# mcu.net
KiCad netlist of a schematic drawn in Altium Designer
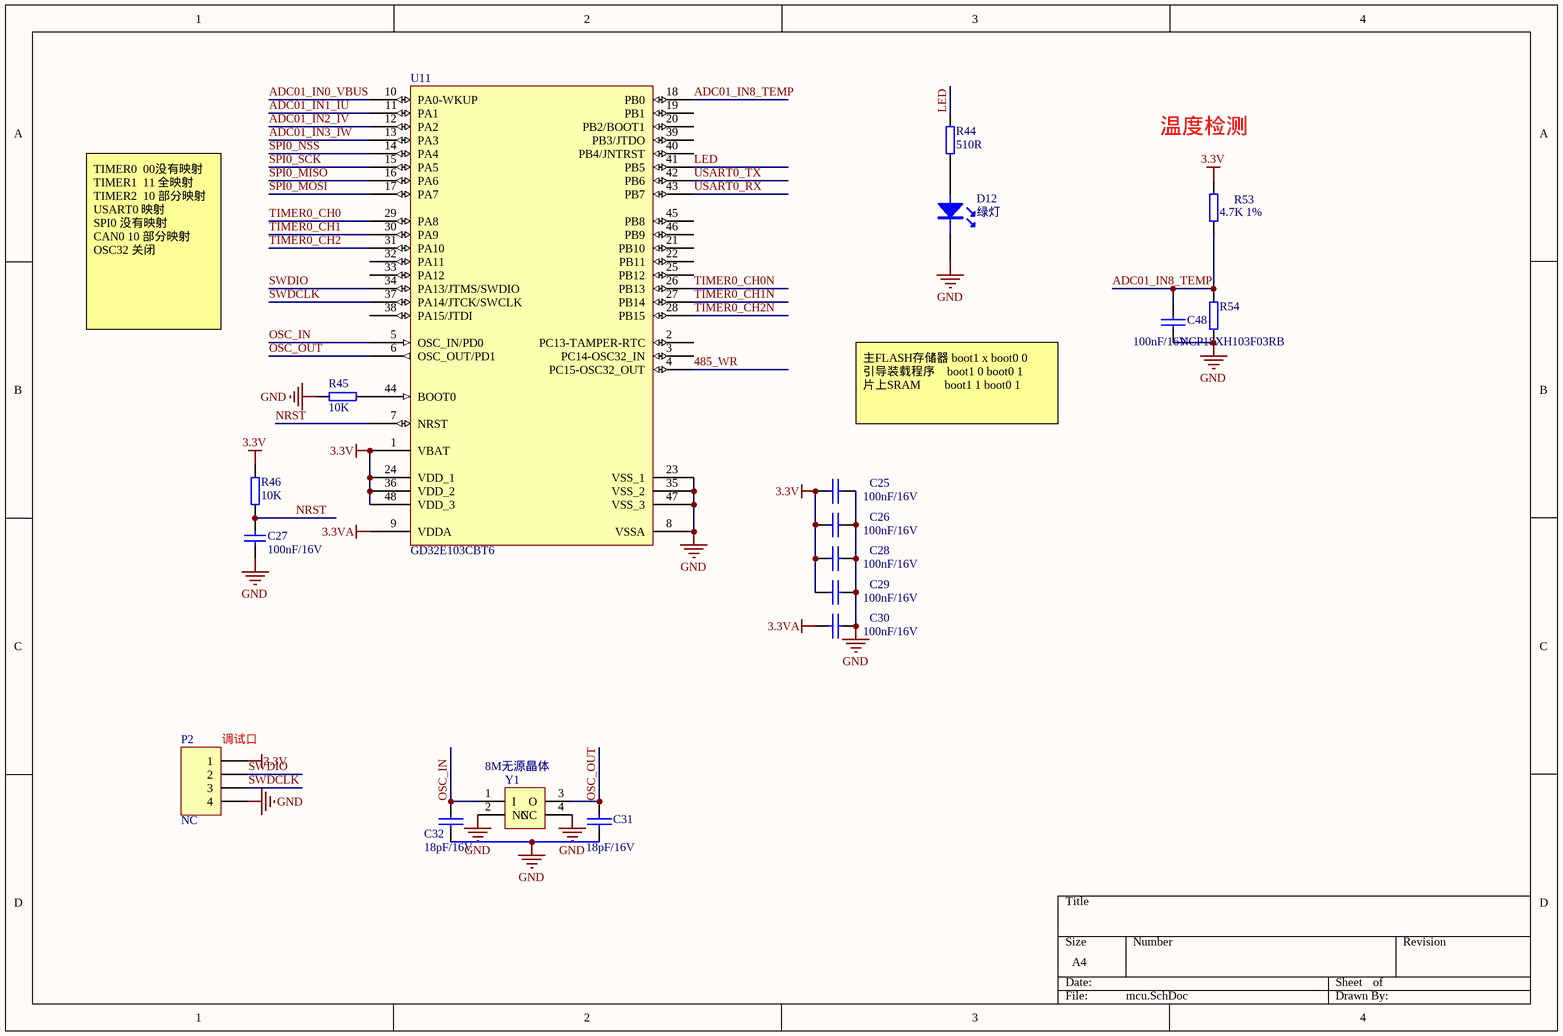
[diagram p0: mcu.SchDoc]

(export (version "E")
  (design (tool "Eeschema 10.0.6"))
  (components
    (comp (ref "C25")
      (value "100nF/16V")
      (footprint "C0402")
      (description "Capacitor")
      (libsource (lib "*") (part "CAP"))
    )
    (comp (ref "C26")
      (value "100nF/16V")
      (footprint "C0402")
      (description "Capacitor")
      (libsource (lib "*") (part "CAP"))
    )
    (comp (ref "C27") (value "100nF/16V") (footprint "C0402") (libsource (lib "zijianku") (part "cap")))
    (comp (ref "C28")
      (value "100nF/16V")
      (footprint "C0402")
      (description "Capacitor")
      (libsource (lib "*") (part "CAP"))
    )
    (comp (ref "C29")
      (value "100nF/16V")
      (footprint "C0402")
      (description "Capacitor")
      (libsource (lib "*") (part "CAP"))
    )
    (comp (ref "C30")
      (value "100nF/16V")
      (footprint "C0402")
      (description "Capacitor")
      (libsource (lib "*") (part "CAP"))
    )
    (comp (ref "C31")
      (value "18pF/16V")
      (footprint "C0402")
      (description "Capacitor")
      (libsource (lib "*") (part "CAP"))
    )
    (comp (ref "C32")
      (value "18pF/16V")
      (footprint "C0402")
      (description "Capacitor")
      (libsource (lib "*") (part "CAP"))
    )
    (comp (ref "C48")
      (value "100nF/16V")
      (footprint "C0402")
      (description "Capacitor")
      (libsource (lib "*") (part "CAP"))
    )
    (comp (ref "D12")
      (value "绿灯")
      (footprint "LED_0603")
      (description "绿灯led")
      (libsource (lib "*") (part "LED"))
    )
    (comp (ref "P2")
      (value "NC")
      (footprint "2.0*4")
      (description "空，无器件")
      (fields (field (name "PUBLISHER") "Altium Limited"))
      (libsource (lib "COMMON") (part "排针2mm,1*4"))
    )
    (comp (ref "R44") (value "510R") (footprint "R0402") (libsource (lib "*") (part "R")))
    (comp (ref "R45") (value "10K") (footprint "R0402") (libsource (lib "zijianku") (part "Resistance")))
    (comp (ref "R46") (value "10K") (footprint "R0402") (libsource (lib "zijianku") (part "Resistance")))
    (comp (ref "R53") (value "4.7K 1%") (footprint "R0402") (libsource (lib "*") (part "R")))
    (comp (ref "R54") (value "NCP18XH103F03RB") (footprint "R0603") (libsource (lib "*") (part "R")))
    (comp (ref "U11")
      (value "GD32E103CBT6")
      (footprint "LQFP-48")
      (fields (field (name "PUBLISHER") "*"))
      (libsource (lib "GD32 MCU") (part "GD32E103CxT6"))
    )
    (comp (ref "Y1") (value "8M无源晶体") (footprint "5032 4pin") (libsource (lib "*") (part "OSC24")))
  )
  (nets
    (net (code "1") (name "/485_WR") (class "Default")
      (node (ref "U11") (pin "4") (pinfunction "PC15-OSC32_OUT_4") (pintype "bidirectional"))
    )
    (net (code "2") (name "/ADC01_IN0_VBUS") (class "Default")
      (node (ref "U11") (pin "10") (pinfunction "PA0-WKUP_10") (pintype "bidirectional"))
    )
    (net (code "3") (name "/ADC01_IN1_IU") (class "Default")
      (node (ref "U11") (pin "11") (pinfunction "PA1_11") (pintype "bidirectional"))
    )
    (net (code "4") (name "/ADC01_IN2_IV") (class "Default")
      (node (ref "U11") (pin "12") (pinfunction "PA2_12") (pintype "bidirectional"))
    )
    (net (code "5") (name "/ADC01_IN3_IW") (class "Default")
      (node (ref "U11") (pin "13") (pinfunction "PA3_13") (pintype "bidirectional"))
    )
    (net (code "6") (name "/ADC01_IN8_TEMP") (class "Default")
      (node (ref "C48") (pin "1") (pinfunction "1_1") (pintype "passive"))
      (node (ref "R53") (pin "1") (pinfunction "1_1") (pintype "passive"))
      (node (ref "R54") (pin "2") (pinfunction "2_2") (pintype "passive"))
      (node (ref "U11") (pin "18") (pinfunction "PB0_18") (pintype "bidirectional"))
    )
    (net (code "7") (name "/LED") (class "Default")
      (node (ref "R44") (pin "1") (pinfunction "1_1") (pintype "passive"))
      (node (ref "U11") (pin "41") (pinfunction "PB5_41") (pintype "bidirectional"))
    )
    (net (code "8") (name "/NRST") (class "Default")
      (node (ref "C27") (pin "2") (pinfunction "1_2") (pintype "passive"))
      (node (ref "R46") (pin "1") (pintype "passive"))
      (node (ref "U11") (pin "7") (pinfunction "NRST_7") (pintype "bidirectional"))
    )
    (net (code "9") (name "/OSC_IN") (class "Default")
      (node (ref "C32") (pin "2") (pinfunction "2_2") (pintype "passive"))
      (node (ref "U11") (pin "5") (pinfunction "OSC_IN/PD0_5") (pintype "input"))
      (node (ref "Y1") (pin "1") (pinfunction "I_1") (pintype "passive"))
    )
    (net (code "10") (name "/OSC_OUT") (class "Default")
      (node (ref "C31") (pin "2") (pinfunction "2_2") (pintype "passive"))
      (node (ref "U11") (pin "6") (pinfunction "OSC_OUT/PD1_6") (pintype "output"))
      (node (ref "Y1") (pin "3") (pinfunction "O_3") (pintype "passive"))
    )
    (net (code "11") (name "/SPI0_MISO") (class "Default")
      (node (ref "U11") (pin "16") (pinfunction "PA6_16") (pintype "bidirectional"))
    )
    (net (code "12") (name "/SPI0_MOSI") (class "Default")
      (node (ref "U11") (pin "17") (pinfunction "PA7_17") (pintype "bidirectional"))
    )
    (net (code "13") (name "/SPI0_NSS") (class "Default")
      (node (ref "U11") (pin "14") (pinfunction "PA4_14") (pintype "bidirectional"))
    )
    (net (code "14") (name "/SPI0_SCK") (class "Default")
      (node (ref "U11") (pin "15") (pinfunction "PA5_15") (pintype "bidirectional"))
    )
    (net (code "15") (name "/SWDCLK") (class "Default")
      (node (ref "P2") (pin "3") (pinfunction "3_3") (pintype "passive"))
      (node (ref "U11") (pin "37") (pinfunction "PA14/JTCK/SWCLK_37") (pintype "bidirectional"))
    )
    (net (code "16") (name "/SWDIO") (class "Default")
      (node (ref "P2") (pin "2") (pinfunction "2_2") (pintype "passive"))
      (node (ref "U11") (pin "34") (pinfunction "PA13/JTMS/SWDIO_34") (pintype "bidirectional"))
    )
    (net (code "17") (name "/TIMER0_CH0") (class "Default")
      (node (ref "U11") (pin "29") (pinfunction "PA8_29") (pintype "bidirectional"))
    )
    (net (code "18") (name "/TIMER0_CH0N") (class "Default")
      (node (ref "U11") (pin "26") (pinfunction "PB13_26") (pintype "bidirectional"))
    )
    (net (code "19") (name "/TIMER0_CH1") (class "Default")
      (node (ref "U11") (pin "30") (pinfunction "PA9_30") (pintype "bidirectional"))
    )
    (net (code "20") (name "/TIMER0_CH1N") (class "Default")
      (node (ref "U11") (pin "27") (pinfunction "PB14_27") (pintype "bidirectional"))
    )
    (net (code "21") (name "/TIMER0_CH2") (class "Default")
      (node (ref "U11") (pin "31") (pinfunction "PA10_31") (pintype "bidirectional"))
    )
    (net (code "22") (name "/TIMER0_CH2N") (class "Default")
      (node (ref "U11") (pin "28") (pinfunction "PB15_28") (pintype "bidirectional"))
    )
    (net (code "23") (name "/USART0_RX") (class "Default")
      (node (ref "U11") (pin "43") (pinfunction "PB7_43") (pintype "bidirectional"))
    )
    (net (code "24") (name "/USART0_TX") (class "Default")
      (node (ref "U11") (pin "42") (pinfunction "PB6_42") (pintype "bidirectional"))
    )
    (net (code "25") (name "3.3V") (class "Default")
      (node (ref "C25") (pin "2") (pinfunction "2_2") (pintype "passive"))
      (node (ref "C26") (pin "2") (pinfunction "2_2") (pintype "passive"))
      (node (ref "C28") (pin "2") (pinfunction "2_2") (pintype "passive"))
      (node (ref "C29") (pin "2") (pinfunction "2_2") (pintype "passive"))
      (node (ref "P2") (pin "1") (pinfunction "1_1") (pintype "passive"))
      (node (ref "R46") (pin "2") (pintype "passive"))
      (node (ref "R53") (pin "2") (pinfunction "2_2") (pintype "passive"))
      (node (ref "U11") (pin "1") (pinfunction "VBAT_1") (pintype "power_in"))
      (node (ref "U11") (pin "24") (pinfunction "VDD_1_24") (pintype "power_in"))
      (node (ref "U11") (pin "36") (pinfunction "VDD_2_36") (pintype "power_in"))
      (node (ref "U11") (pin "48") (pinfunction "VDD_3_48") (pintype "power_in"))
    )
    (net (code "26") (name "3.3VA") (class "Default")
      (node (ref "C30") (pin "2") (pinfunction "2_2") (pintype "passive"))
      (node (ref "U11") (pin "9") (pinfunction "VDDA_9") (pintype "power_in"))
    )
    (net (code "27") (name "GND") (class "Default")
      (node (ref "C25") (pin "1") (pinfunction "1_1") (pintype "passive"))
      (node (ref "C26") (pin "1") (pinfunction "1_1") (pintype "passive"))
      (node (ref "C27") (pin "1") (pinfunction "0_1") (pintype "passive"))
      (node (ref "C28") (pin "1") (pinfunction "1_1") (pintype "passive"))
      (node (ref "C29") (pin "1") (pinfunction "1_1") (pintype "passive"))
      (node (ref "C30") (pin "1") (pinfunction "1_1") (pintype "passive"))
      (node (ref "C31") (pin "1") (pinfunction "1_1") (pintype "passive"))
      (node (ref "C32") (pin "1") (pinfunction "1_1") (pintype "passive"))
      (node (ref "C48") (pin "2") (pinfunction "2_2") (pintype "passive"))
      (node (ref "D12") (pin "2") (pinfunction "K_2") (pintype "passive"))
      (node (ref "P2") (pin "4") (pinfunction "4_4") (pintype "passive"))
      (node (ref "R45") (pin "1") (pintype "passive"))
      (node (ref "R54") (pin "1") (pinfunction "1_1") (pintype "passive"))
      (node (ref "U11") (pin "23") (pinfunction "VSS_1_23") (pintype "power_in"))
      (node (ref "U11") (pin "35") (pinfunction "VSS_2_35") (pintype "power_in"))
      (node (ref "U11") (pin "47") (pinfunction "VSS_3_47") (pintype "power_in"))
      (node (ref "U11") (pin "8") (pinfunction "VSSA_8") (pintype "power_in"))
      (node (ref "Y1") (pin "2") (pinfunction "NC_2") (pintype "passive"))
      (node (ref "Y1") (pin "4") (pinfunction "NC_4") (pintype "passive"))
    )
    (net (code "28") (name "Net-(D12-A)") (class "Default")
      (node (ref "D12") (pin "1") (pinfunction "A_1") (pintype "passive"))
      (node (ref "R44") (pin "2") (pinfunction "2_2") (pintype "passive"))
    )
    (net (code "29") (name "Net-(U11-BOOT0)") (class "Default")
      (node (ref "R45") (pin "2") (pintype "passive"))
      (node (ref "U11") (pin "44") (pinfunction "BOOT0_44") (pintype "input"))
    )
    (net (code "30") (name "unconnected-(U11-PA11-Pad32)") (class "Default")
      (node (ref "U11") (pin "32") (pinfunction "PA11_32") (pintype "bidirectional"))
    )
    (net (code "31") (name "unconnected-(U11-PA12-Pad33)") (class "Default")
      (node (ref "U11") (pin "33") (pinfunction "PA12_33") (pintype "bidirectional"))
    )
    (net (code "32") (name "unconnected-(U11-PA15{slash}JTDI-Pad38)") (class "Default")
      (node (ref "U11") (pin "38") (pinfunction "PA15/JTDI_38") (pintype "bidirectional"))
    )
    (net (code "33") (name "unconnected-(U11-PB1-Pad19)") (class "Default")
      (node (ref "U11") (pin "19") (pinfunction "PB1_19") (pintype "bidirectional"))
    )
    (net (code "34") (name "unconnected-(U11-PB2{slash}BOOT1-Pad20)") (class "Default")
      (node (ref "U11") (pin "20") (pinfunction "PB2/BOOT1_20") (pintype "bidirectional"))
    )
    (net (code "35") (name "unconnected-(U11-PB3{slash}JTDO-Pad39)") (class "Default")
      (node (ref "U11") (pin "39") (pinfunction "PB3/JTDO_39") (pintype "bidirectional"))
    )
    (net (code "36") (name "unconnected-(U11-PB4{slash}JNTRST-Pad40)") (class "Default")
      (node (ref "U11") (pin "40") (pinfunction "PB4/JNTRST_40") (pintype "bidirectional"))
    )
    (net (code "37") (name "unconnected-(U11-PB8-Pad45)") (class "Default")
      (node (ref "U11") (pin "45") (pinfunction "PB8_45") (pintype "bidirectional"))
    )
    (net (code "38") (name "unconnected-(U11-PB9-Pad46)") (class "Default")
      (node (ref "U11") (pin "46") (pinfunction "PB9_46") (pintype "bidirectional"))
    )
    (net (code "39") (name "unconnected-(U11-PB10-Pad21)") (class "Default")
      (node (ref "U11") (pin "21") (pinfunction "PB10_21") (pintype "bidirectional"))
    )
    (net (code "40") (name "unconnected-(U11-PB11-Pad22)") (class "Default")
      (node (ref "U11") (pin "22") (pinfunction "PB11_22") (pintype "bidirectional"))
    )
    (net (code "41") (name "unconnected-(U11-PB12-Pad25)") (class "Default")
      (node (ref "U11") (pin "25") (pinfunction "PB12_25") (pintype "bidirectional"))
    )
    (net (code "42") (name "unconnected-(U11-PC13-TAMPER-RTC-Pad2)") (class "Default")
      (node (ref "U11") (pin "2") (pinfunction "PC13-TAMPER-RTC_2") (pintype "bidirectional"))
    )
    (net (code "43") (name "unconnected-(U11-PC14-OSC32_IN-Pad3)") (class "Default")
      (node (ref "U11") (pin "3") (pinfunction "PC14-OSC32_IN_3") (pintype "bidirectional"))
    )
  )
)
